# CPU.net
KiCad netlist of a schematic drawn in Altium Designer
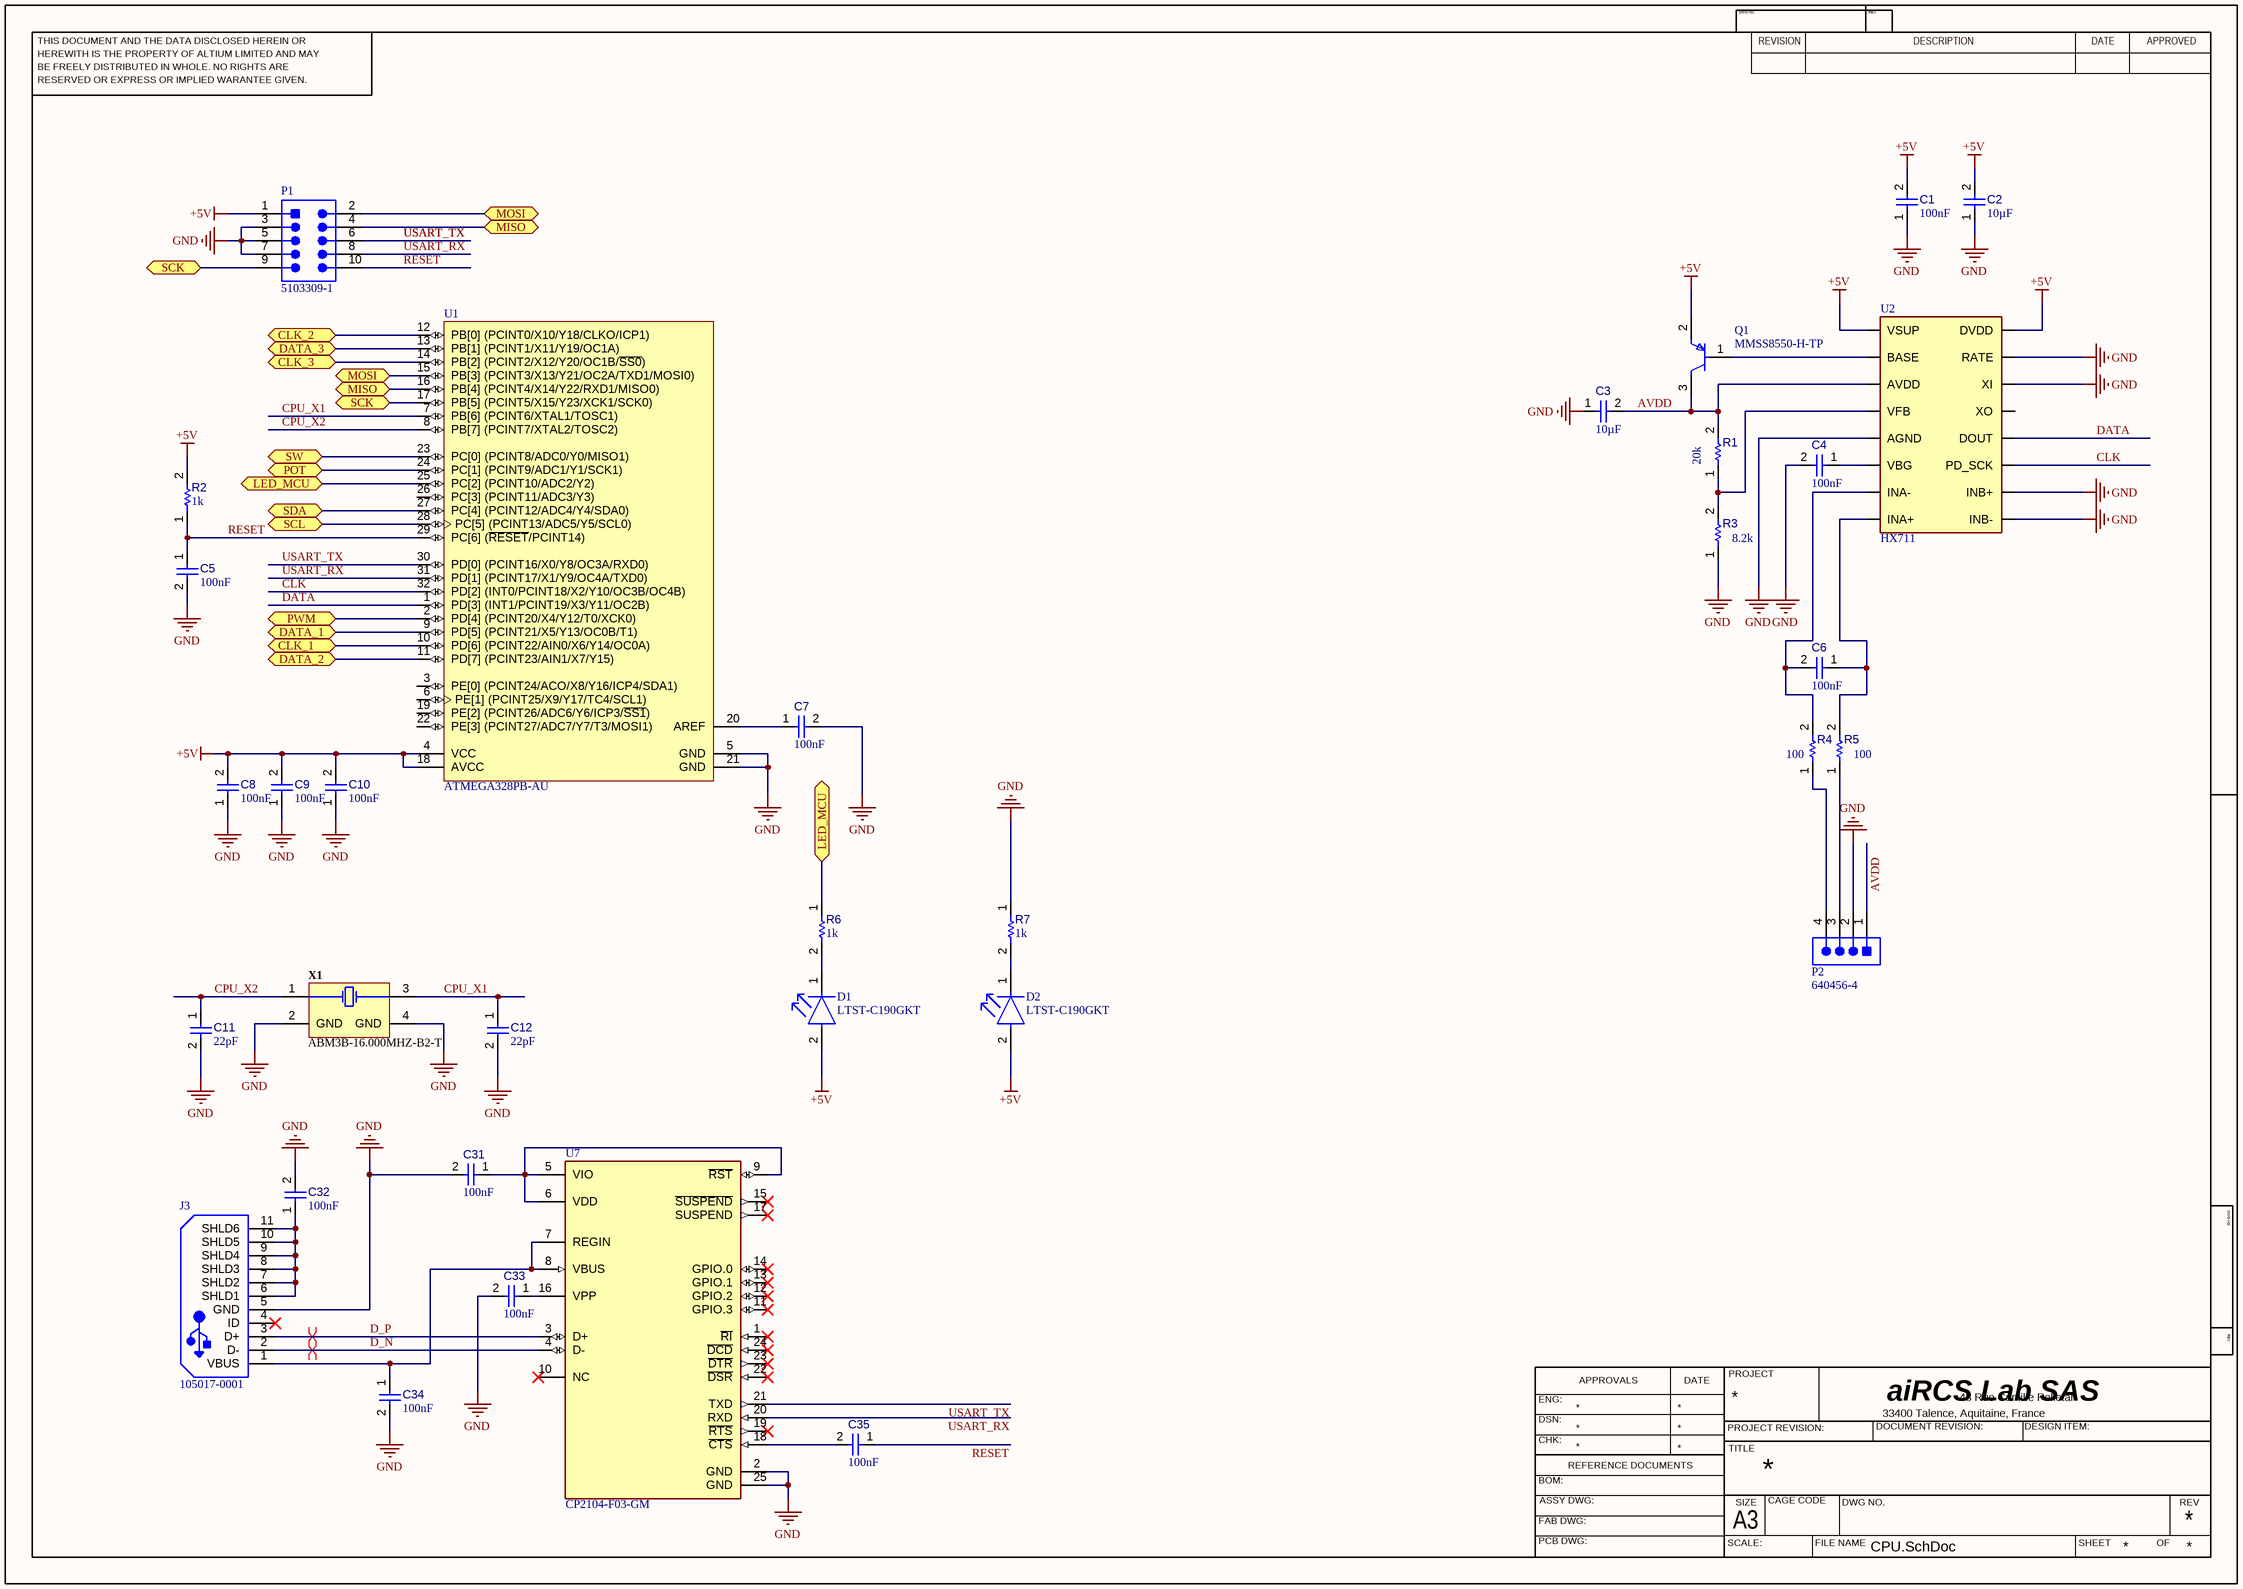
[diagram p0: CPU.SchDoc]

(export (version "E")
  (design (tool "Eeschema 10.0.6"))
  (components
    (comp (ref "C1")
      (value "100nF")
      (footprint "CAPC0402(1005)60_L")
      (description "Chip Capacitor, 100nF +/-20%, 50V, 0402, Thickness 0.6 mm")
      (fields (field (name "TOLERANCE") "10%") (field (name "Comment") "Capacitor 100nF +/-20% 50V 0402"))
      (libsource (lib "Kariboo") (part "CAP-NP-2"))
    )
    (comp (ref "C2")
      (value "10µF")
      (footprint "CAPC0402(1005)60_L")
      (description "Chip Capacitor, 10µF +/-40%, 6.3V, 0402, Thickness 0.6 mm")
      (fields (field (name "TOLERANCE") "10%") (field (name "Comment") "Capacitor 10µF +/-40% 6.3V 0402"))
      (libsource (lib "Kariboo") (part "CAP-NP-2"))
    )
    (comp (ref "C3")
      (value "10µF")
      (footprint "CAPC0402(1005)60_L")
      (description "Chip Capacitor, 10µF +/-40%, 6.3V, 0402, Thickness 0.6 mm")
      (fields (field (name "TOLERANCE") "10%") (field (name "Comment") "Capacitor 10µF +/-40% 6.3V 0402"))
      (libsource (lib "Kariboo") (part "CAP-NP-2"))
    )
    (comp (ref "C4")
      (value "100nF")
      (footprint "CAPC0402(1005)60_L")
      (description "Chip Capacitor, 100nF +/-20%, 50V, 0402, Thickness 0.6 mm")
      (fields (field (name "TOLERANCE") "10%") (field (name "Comment") "Capacitor 100nF +/-20% 50V 0402"))
      (libsource (lib "Kariboo") (part "CAP-NP-2"))
    )
    (comp (ref "C5")
      (value "100nF")
      (footprint "CAPC0402(1005)60_L")
      (description "Chip Capacitor, 100nF +/-20%, 50V, 0402, Thickness 0.6 mm")
      (fields (field (name "TOLERANCE") "10%") (field (name "Comment") "Capacitor 100nF +/-20% 50V 0402"))
      (libsource (lib "Kariboo") (part "CAP-NP-2"))
    )
    (comp (ref "C6")
      (value "100nF")
      (footprint "CAPC0402(1005)60_L")
      (description "Chip Capacitor, 100nF +/-20%, 50V, 0402, Thickness 0.6 mm")
      (fields (field (name "TOLERANCE") "10%") (field (name "Comment") "Capacitor 100nF +/-20% 50V 0402"))
      (libsource (lib "Kariboo") (part "CAP-NP-2"))
    )
    (comp (ref "C7")
      (value "100nF")
      (footprint "CAPC0402(1005)60_L")
      (description "Chip Capacitor, 100nF +/-20%, 50V, 0402, Thickness 0.6 mm")
      (fields (field (name "TOLERANCE") "10%") (field (name "Comment") "Capacitor 100nF +/-20% 50V 0402"))
      (libsource (lib "Kariboo") (part "CAP-NP-2"))
    )
    (comp (ref "C8")
      (value "100nF")
      (footprint "CAPC0402(1005)60_L")
      (description "Chip Capacitor, 100nF +/-20%, 50V, 0402, Thickness 0.6 mm")
      (fields (field (name "TOLERANCE") "10%") (field (name "Comment") "Capacitor 100nF +/-20% 50V 0402"))
      (libsource (lib "Kariboo") (part "CAP-NP-2"))
    )
    (comp (ref "C9")
      (value "100nF")
      (footprint "CAPC0402(1005)60_L")
      (description "Chip Capacitor, 100nF +/-20%, 50V, 0402, Thickness 0.6 mm")
      (fields (field (name "TOLERANCE") "10%") (field (name "Comment") "Capacitor 100nF +/-20% 50V 0402"))
      (libsource (lib "Kariboo") (part "CAP-NP-2"))
    )
    (comp (ref "C10")
      (value "100nF")
      (footprint "CAPC0402(1005)60_L")
      (description "Chip Capacitor, 100nF +/-20%, 50V, 0402, Thickness 0.6 mm")
      (fields (field (name "TOLERANCE") "10%") (field (name "Comment") "Capacitor 100nF +/-20% 50V 0402"))
      (libsource (lib "Kariboo") (part "CAP-NP-2"))
    )
    (comp (ref "C11")
      (value "22pF")
      (footprint "CAPC0603(1608)100_L")
      (description "Chip Capacitor, 1µF +/-40%, 50V, 0603, Thickness 1 mm")
      (fields (field (name "TOLERANCE") "10%") (field (name "Comment") "Capacitor 1µF +/-40% 50V 0603"))
      (libsource (lib "Kariboo") (part "CAP-NP-2"))
    )
    (comp (ref "C12")
      (value "22pF")
      (footprint "CAPC0603(1608)100_L")
      (description "Chip Capacitor, 1µF +/-40%, 50V, 0603, Thickness 1 mm")
      (fields (field (name "TOLERANCE") "10%") (field (name "Comment") "Capacitor 1µF +/-40% 50V 0603"))
      (libsource (lib "Kariboo") (part "CAP-NP-2"))
    )
    (comp (ref "C31")
      (value "100nF")
      (footprint "CAPC0603(1608)100_L")
      (description "Chip Capacitor, 1µF +/-40%, 50V, 0603, Thickness 1 mm")
      (fields (field (name "TOLERANCE") "10%") (field (name "Comment") "Capacitor 1µF +/-40% 50V 0603"))
      (libsource (lib "Kariboo") (part "CAP-NP-2"))
    )
    (comp (ref "C32")
      (value "100nF")
      (footprint "CAPC0603(1608)100_L")
      (description "Chip Capacitor, 1µF +/-40%, 50V, 0603, Thickness 1 mm")
      (fields (field (name "TOLERANCE") "10%") (field (name "Comment") "Capacitor 1µF +/-40% 50V 0603"))
      (libsource (lib "Kariboo") (part "CAP-NP-2"))
    )
    (comp (ref "C33")
      (value "100nF")
      (footprint "CAPC0603(1608)100_L")
      (description "Chip Capacitor, 1µF +/-40%, 50V, 0603, Thickness 1 mm")
      (fields (field (name "TOLERANCE") "10%") (field (name "Comment") "Capacitor 1µF +/-40% 50V 0603"))
      (libsource (lib "Kariboo") (part "CAP-NP-2"))
    )
    (comp (ref "C34")
      (value "100nF")
      (footprint "CAPC0603(1608)100_L")
      (description "Chip Capacitor, 1µF +/-40%, 50V, 0603, Thickness 1 mm")
      (fields (field (name "TOLERANCE") "10%") (field (name "Comment") "Capacitor 1µF +/-40% 50V 0603"))
      (libsource (lib "Kariboo") (part "CAP-NP-2"))
    )
    (comp (ref "C35")
      (value "100nF")
      (footprint "CAPC0603(1608)100_L")
      (description "Chip Capacitor, 1µF +/-40%, 50V, 0603, Thickness 1 mm")
      (fields (field (name "TOLERANCE") "10%") (field (name "Comment") "Capacitor 1µF +/-40% 50V 0603"))
      (libsource (lib "Kariboo") (part "CAP-NP-2"))
    )
    (comp (ref "D1")
      (value "LTST-C190GKT")
      (footprint "FP-LTST-C190GKT-MFG")
      (description "LED GREEN CLEAR CHIP SMD")
      (fields (field (name "VOLTAGE") "2V"))
      (libsource (lib "Altium Content Vault") (part "8706943c75ba83719d021d2fdc84c58"))
    )
    (comp (ref "D2")
      (value "LTST-C190GKT")
      (footprint "FP-LTST-C190GKT-MFG")
      (description "LED GREEN CLEAR CHIP SMD")
      (fields (field (name "VOLTAGE") "2V"))
      (libsource (lib "Altium Content Vault") (part "8706943c75ba83719d021d2fdc84c58"))
    )
    (comp (ref "J3")
      (value "105017-0001")
      (footprint "USB-MICRO-B_V")
      (fields (field (name "MANUFACTURER") "Molex"))
      (libsource (lib "Altium Content Vault") (part "USB-5-6SHLD"))
    )
    (comp (ref "P1")
      (value "5103309-1")
      (footprint "TECO-5103309-1_V")
      (fields (field (name "MANUFACTURER") "TE Connectivity"))
      (libsource (lib "Altium Content Vault") (part "CN-2P-M-R10"))
    )
    (comp (ref "P2")
      (value "640456-4")
      (footprint "TECO-640456-4")
      (description "Male Header, Pitch 2.54 mm, 1 x 4 Position, Height 10.03 mm, Tail Length 3.56 mm, RoHS, Bulk")
      (fields (field (name "MANUFACTURER") "TE Connectivity"))
      (libsource (lib "Altium Content Vault") (part "CN-1P-M-R4"))
    )
    (comp (ref "Q1")
      (value "MMSS8550-H-TP")
      (footprint "FP-SOT-23-IPC_B")
      (description "TRANS PNP 25V 1.5A SOT23")
      (libsource (lib "Altium Content Vault") (part "0e8486ed3b47d9c69b8404ba87cf0f7"))
    )
    (comp (ref "R1")
      (value "20k")
      (footprint "RESC0402(1005)_L")
      (description "Resistor 0402")
      (fields (field (name "Comment") "RES"))
      (libsource (lib "Kariboo") (part "0R2J"))
    )
    (comp (ref "R2") (value "1k") (footprint "RESC0402(1005)_L") (libsource (lib "Kariboo") (part "0R2J")))
    (comp (ref "R3")
      (value "8.2k")
      (footprint "RESC0402(1005)_L")
      (description "Resistor 0402")
      (libsource (lib "Kariboo") (part "0R2J"))
    )
    (comp (ref "R4") (value "100") (footprint "RESC0402(1005)_L") (libsource (lib "Kariboo") (part "0R2J")))
    (comp (ref "R5") (value "100") (footprint "RESC0402(1005)_L") (libsource (lib "Kariboo") (part "0R2J")))
    (comp (ref "R6") (value "1k") (footprint "RESC0402(1005)_L") (libsource (lib "Kariboo") (part "0R2J")))
    (comp (ref "R7") (value "1k") (footprint "RESC0402(1005)_L") (libsource (lib "Kariboo") (part "0R2J")))
    (comp (ref "U1")
      (value "ATMEGA328PB-AU")
      (footprint "ATML-32A_L")
      (fields (field (name "MANUFACTURER") "Microchip"))
      (libsource (lib "Altium Content Vault") (part "ATML-ATMEGA328PB-32A"))
    )
    (comp (ref "U2")
      (value "HX711")
      (footprint "SOP127P600X180-16N")
      (fields (field (name "MF") "AVIA SEMICONDUCTOR"))
      (libsource (lib "HX711") (part "HX711"))
    )
    (comp (ref "U7")
      (value "CP2104-F03-GM")
      (footprint "FP-CP2104-F03-GM-MFG")
      (description "IC SGL USB-TO-UART BRIDGE 24QFN")
      (libsource (lib "Altium Content Vault") (part "36aa9e967c7f1036f799a443da3d357"))
    )
    (comp (ref "X1")
      (value "ABM3B-16.000MHZ-B2-T")
      (footprint "ABRA-ABM3B-4_V")
      (description "Ceramic SMD Crystal, 16 MHz, +/- 20 ppm, 50 Ohm, -20 to 70 degC, 4-Pin SMD, RoHS, Tape and Reel")
      (fields (field (name "TOLERANCE") "30%"))
      (libsource (lib "Altium Content Vault") (part "XTAL-1-3-4"))
    )
  )
  (nets
    (net (code "1") (name "+5V") (class "Default")
      (node (ref "C1") (pin "2") (pinfunction "2_2") (pintype "passive"))
      (node (ref "C10") (pin "2") (pinfunction "2_2") (pintype "passive"))
      (node (ref "C2") (pin "2") (pinfunction "2_2") (pintype "passive"))
      (node (ref "C8") (pin "2") (pinfunction "2_2") (pintype "passive"))
      (node (ref "C9") (pin "2") (pinfunction "2_2") (pintype "passive"))
      (node (ref "D1") (pin "2") (pinfunction "A_2") (pintype "passive"))
      (node (ref "D2") (pin "2") (pinfunction "A_2") (pintype "passive"))
      (node (ref "P1") (pin "1") (pinfunction "1_1") (pintype "passive"))
      (node (ref "Q1") (pin "2") (pinfunction "E_2") (pintype "passive"))
      (node (ref "R2") (pin "2") (pinfunction "2_2") (pintype "passive"))
      (node (ref "U1") (pin "18") (pinfunction "AVCC_18") (pintype "power_in"))
      (node (ref "U1") (pin "4") (pinfunction "VCC_4") (pintype "power_in"))
      (node (ref "U2") (pin "1") (pinfunction "VSUP_1") (pintype "bidirectional"))
      (node (ref "U2") (pin "16") (pinfunction "DVDD_16") (pintype "bidirectional"))
    )
    (net (code "2") (name "/AVDD") (class "Default")
      (node (ref "C3") (pin "2") (pinfunction "2_2") (pintype "passive"))
      (node (ref "P2") (pin "1") (pinfunction "1_1") (pintype "passive"))
      (node (ref "Q1") (pin "3") (pinfunction "C_3") (pintype "passive"))
      (node (ref "R1") (pin "2") (pinfunction "2_2") (pintype "passive"))
      (node (ref "U2") (pin "3") (pinfunction "AVDD_3") (pintype "bidirectional"))
    )
    (net (code "3") (name "/CLK") (class "Default")
      (node (ref "U1") (pin "32") (pinfunction "PD[2]_(INT0/PCINT18/X2/Y10/OC3B/OC4B)_32") (pintype "bidirectional"))
      (node (ref "U2") (pin "11") (pinfunction "PD_SCK_11") (pintype "bidirectional"))
    )
    (net (code "4") (name "/CLK_1") (class "Default")
      (node (ref "U1") (pin "10") (pinfunction "PD[6]_(PCINT22/AIN0/X6/Y14/OC0A)_10") (pintype "bidirectional"))
    )
    (net (code "5") (name "/CLK_2") (class "Default")
      (node (ref "U1") (pin "12") (pinfunction "PB[0]_(PCINT0/X10/Y18/CLKO/ICP1)_12") (pintype "bidirectional"))
    )
    (net (code "6") (name "/CLK_3") (class "Default")
      (node (ref "U1") (pin "14") (pinfunction "PB[2]_(PCINT2/X12/Y20/OC1B/~{SS0})_14") (pintype "bidirectional"))
    )
    (net (code "7") (name "/CPU_X1") (class "Default")
      (node (ref "C12") (pin "1") (pinfunction "1_1") (pintype "passive"))
      (node (ref "U1") (pin "7") (pinfunction "PB[6]_(PCINT6/XTAL1/TOSC1)_7") (pintype "bidirectional"))
      (node (ref "X1") (pin "3") (pinfunction "X2_3") (pintype "passive"))
    )
    (net (code "8") (name "/CPU_X2") (class "Default")
      (node (ref "C11") (pin "1") (pinfunction "1_1") (pintype "passive"))
      (node (ref "U1") (pin "8") (pinfunction "PB[7]_(PCINT7/XTAL2/TOSC2)_8") (pintype "bidirectional"))
      (node (ref "X1") (pin "1") (pinfunction "X1_1") (pintype "passive"))
    )
    (net (code "9") (name "/DATA") (class "Default")
      (node (ref "U1") (pin "1") (pinfunction "PD[3]_(INT1/PCINT19/X3/Y11/OC2B)_1") (pintype "bidirectional"))
      (node (ref "U2") (pin "12") (pinfunction "DOUT_12") (pintype "bidirectional"))
    )
    (net (code "10") (name "/DATA_1") (class "Default")
      (node (ref "U1") (pin "9") (pinfunction "PD[5]_(PCINT21/X5/Y13/OC0B/T1)_9") (pintype "bidirectional"))
    )
    (net (code "11") (name "/DATA_2") (class "Default")
      (node (ref "U1") (pin "11") (pinfunction "PD[7]_(PCINT23/AIN1/X7/Y15)_11") (pintype "bidirectional"))
    )
    (net (code "12") (name "/DATA_3") (class "Default")
      (node (ref "U1") (pin "13") (pinfunction "PB[1]_(PCINT1/X11/Y19/OC1A)_13") (pintype "bidirectional"))
    )
    (net (code "13") (name "/D_N") (class "Default")
      (node (ref "J3") (pin "2") (pinfunction "D-_2") (pintype "passive"))
      (node (ref "U7") (pin "4") (pinfunction "D-_4") (pintype "bidirectional"))
    )
    (net (code "14") (name "/D_P") (class "Default")
      (node (ref "J3") (pin "3") (pinfunction "D+_3") (pintype "passive"))
      (node (ref "U7") (pin "3") (pinfunction "D+_3") (pintype "bidirectional"))
    )
    (net (code "15") (name "/LED_MCU") (class "Default")
      (node (ref "R6") (pin "1") (pinfunction "1_1") (pintype "passive"))
      (node (ref "U1") (pin "25") (pinfunction "PC[2]_(PCINT10/ADC2/Y2)_25") (pintype "bidirectional"))
    )
    (net (code "16") (name "/MISO") (class "Default")
      (node (ref "P1") (pin "4") (pinfunction "4_4") (pintype "passive"))
      (node (ref "U1") (pin "16") (pinfunction "PB[4]_(PCINT4/X14/Y22/RXD1/MISO0)_16") (pintype "bidirectional"))
    )
    (net (code "17") (name "/MOSI") (class "Default")
      (node (ref "P1") (pin "2") (pinfunction "2_2") (pintype "passive"))
      (node (ref "U1") (pin "15") (pinfunction "PB[3]_(PCINT3/X13/Y21/OC2A/TXD1/MOSI0)_15") (pintype "bidirectional"))
    )
    (net (code "18") (name "/POT") (class "Default")
      (node (ref "U1") (pin "24") (pinfunction "PC[1]_(PCINT9/ADC1/Y1/SCK1)_24") (pintype "bidirectional"))
    )
    (net (code "19") (name "/PWM") (class "Default")
      (node (ref "U1") (pin "2") (pinfunction "PD[4]_(PCINT20/X4/Y12/T0/XCK0)_2") (pintype "bidirectional"))
    )
    (net (code "20") (name "/RESET") (class "Default")
      (node (ref "C35") (pin "1") (pinfunction "1_1") (pintype "passive"))
      (node (ref "C5") (pin "1") (pinfunction "1_1") (pintype "passive"))
      (node (ref "P1") (pin "10") (pinfunction "10_10") (pintype "passive"))
      (node (ref "R2") (pin "1") (pinfunction "1_1") (pintype "passive"))
      (node (ref "U1") (pin "29") (pinfunction "PC[6]_(~{RESET}/PCINT14)_29") (pintype "bidirectional"))
    )
    (net (code "21") (name "/SCK") (class "Default")
      (node (ref "P1") (pin "9") (pinfunction "9_9") (pintype "passive"))
      (node (ref "U1") (pin "17") (pinfunction "PB[5]_(PCINT5/X15/Y23/XCK1/SCK0)_17") (pintype "bidirectional"))
    )
    (net (code "22") (name "/SCL") (class "Default")
      (node (ref "U1") (pin "28") (pinfunction "PC[5]_(PCINT13/ADC5/Y5/SCL0)_28") (pintype "bidirectional"))
    )
    (net (code "23") (name "/SDA") (class "Default")
      (node (ref "U1") (pin "27") (pinfunction "PC[4]_(PCINT12/ADC4/Y4/SDA0)_27") (pintype "bidirectional"))
    )
    (net (code "24") (name "/SW") (class "Default")
      (node (ref "U1") (pin "23") (pinfunction "PC[0]_(PCINT8/ADC0/Y0/MISO1)_23") (pintype "bidirectional"))
    )
    (net (code "25") (name "/USART_RX") (class "Default")
      (node (ref "P1") (pin "8") (pinfunction "8_8") (pintype "passive"))
      (node (ref "U1") (pin "31") (pinfunction "PD[1]_(PCINT17/X1/Y9/OC4A/TXD0)_31") (pintype "bidirectional"))
      (node (ref "U7") (pin "20") (pinfunction "RXD_20") (pintype "input"))
    )
    (net (code "26") (name "/USART_TX") (class "Default")
      (node (ref "P1") (pin "6") (pinfunction "6_6") (pintype "passive"))
      (node (ref "U1") (pin "30") (pinfunction "PD[0]_(PCINT16/X0/Y8/OC3A/RXD0)_30") (pintype "bidirectional"))
      (node (ref "U7") (pin "21") (pinfunction "TXD_21") (pintype "output"))
    )
    (net (code "27") (name "GND") (class "Default")
      (node (ref "C1") (pin "1") (pinfunction "1_1") (pintype "passive"))
      (node (ref "C10") (pin "1") (pinfunction "1_1") (pintype "passive"))
      (node (ref "C11") (pin "2") (pinfunction "2_2") (pintype "passive"))
      (node (ref "C12") (pin "2") (pinfunction "2_2") (pintype "passive"))
      (node (ref "C2") (pin "1") (pinfunction "1_1") (pintype "passive"))
      (node (ref "C3") (pin "1") (pinfunction "1_1") (pintype "passive"))
      (node (ref "C31") (pin "2") (pinfunction "2_2") (pintype "passive"))
      (node (ref "C32") (pin "2") (pinfunction "2_2") (pintype "passive"))
      (node (ref "C33") (pin "2") (pinfunction "2_2") (pintype "passive"))
      (node (ref "C34") (pin "2") (pinfunction "2_2") (pintype "passive"))
      (node (ref "C4") (pin "2") (pinfunction "2_2") (pintype "passive"))
      (node (ref "C5") (pin "2") (pinfunction "2_2") (pintype "passive"))
      (node (ref "C7") (pin "2") (pinfunction "2_2") (pintype "passive"))
      (node (ref "C8") (pin "1") (pinfunction "1_1") (pintype "passive"))
      (node (ref "C9") (pin "1") (pinfunction "1_1") (pintype "passive"))
      (node (ref "J3") (pin "5") (pinfunction "GND_5") (pintype "passive"))
      (node (ref "P1") (pin "3") (pinfunction "3_3") (pintype "passive"))
      (node (ref "P1") (pin "5") (pinfunction "5_5") (pintype "passive"))
      (node (ref "P1") (pin "7") (pinfunction "7_7") (pintype "passive"))
      (node (ref "P2") (pin "2") (pinfunction "2_2") (pintype "passive"))
      (node (ref "R3") (pin "1") (pinfunction "1_1") (pintype "passive"))
      (node (ref "R7") (pin "1") (pinfunction "1_1") (pintype "passive"))
      (node (ref "U1") (pin "21") (pinfunction "GND_21") (pintype "power_in"))
      (node (ref "U1") (pin "5") (pinfunction "GND_5") (pintype "power_in"))
      (node (ref "U2") (pin "10") (pinfunction "INB+_10") (pintype "bidirectional"))
      (node (ref "U2") (pin "14") (pinfunction "XI_14") (pintype "bidirectional"))
      (node (ref "U2") (pin "15") (pinfunction "RATE_15") (pintype "bidirectional"))
      (node (ref "U2") (pin "5") (pinfunction "AGND_5") (pintype "bidirectional"))
      (node (ref "U2") (pin "9") (pinfunction "INB-_9") (pintype "bidirectional"))
      (node (ref "U7") (pin "2") (pinfunction "GND_2") (pintype "power_in"))
      (node (ref "U7") (pin "25") (pinfunction "GND_25") (pintype "power_in"))
      (node (ref "X1") (pin "2") (pinfunction "GND_2") (pintype "power_in"))
      (node (ref "X1") (pin "4") (pinfunction "GND_4") (pintype "power_in"))
    )
    (net (code "28") (name "Net-(D1-C)") (class "Default")
      (node (ref "D1") (pin "1") (pinfunction "C_1") (pintype "passive"))
      (node (ref "R6") (pin "2") (pinfunction "2_2") (pintype "passive"))
    )
    (net (code "29") (name "Net-(D2-C)") (class "Default")
      (node (ref "D2") (pin "1") (pinfunction "C_1") (pintype "passive"))
      (node (ref "R7") (pin "2") (pinfunction "2_2") (pintype "passive"))
    )
    (net (code "30") (name "Net-(J3-SHLD1)") (class "Default")
      (node (ref "C32") (pin "1") (pinfunction "1_1") (pintype "passive"))
      (node (ref "J3") (pin "10") (pinfunction "SHLD5_10") (pintype "passive"))
      (node (ref "J3") (pin "11") (pinfunction "SHLD6_11") (pintype "passive"))
      (node (ref "J3") (pin "6") (pinfunction "SHLD1_6") (pintype "passive"))
      (node (ref "J3") (pin "7") (pinfunction "SHLD2_7") (pintype "passive"))
      (node (ref "J3") (pin "8") (pinfunction "SHLD3_8") (pintype "passive"))
      (node (ref "J3") (pin "9") (pinfunction "SHLD4_9") (pintype "passive"))
    )
    (net (code "31") (name "Net-(J3-VBUS)") (class "Default")
      (node (ref "C34") (pin "1") (pinfunction "1_1") (pintype "passive"))
      (node (ref "J3") (pin "1") (pinfunction "VBUS_1") (pintype "passive"))
      (node (ref "U7") (pin "7") (pinfunction "REGIN_7") (pintype "power_in"))
      (node (ref "U7") (pin "8") (pinfunction "VBUS_8") (pintype "input"))
    )
    (net (code "32") (name "Net-(P2-Pad3)") (class "Default")
      (node (ref "P2") (pin "3") (pinfunction "3_3") (pintype "passive"))
      (node (ref "R5") (pin "1") (pinfunction "1_1") (pintype "passive"))
    )
    (net (code "33") (name "Net-(P2-Pad4)") (class "Default")
      (node (ref "P2") (pin "4") (pinfunction "4_4") (pintype "passive"))
      (node (ref "R4") (pin "1") (pinfunction "1_1") (pintype "passive"))
    )
    (net (code "34") (name "Net-(Q1-B)") (class "Default")
      (node (ref "Q1") (pin "1") (pinfunction "B_1") (pintype "passive"))
      (node (ref "U2") (pin "2") (pinfunction "BASE_2") (pintype "bidirectional"))
    )
    (net (code "35") (name "Net-(U1-AREF)") (class "Default")
      (node (ref "C7") (pin "1") (pinfunction "1_1") (pintype "passive"))
      (node (ref "U1") (pin "20") (pinfunction "AREF_20") (pintype "passive"))
    )
    (net (code "36") (name "Net-(U2-INA+)") (class "Default")
      (node (ref "C6") (pin "1") (pinfunction "1_1") (pintype "passive"))
      (node (ref "R5") (pin "2") (pinfunction "2_2") (pintype "passive"))
      (node (ref "U2") (pin "8") (pinfunction "INA+_8") (pintype "bidirectional"))
    )
    (net (code "37") (name "Net-(U2-INA-)") (class "Default")
      (node (ref "C6") (pin "2") (pinfunction "2_2") (pintype "passive"))
      (node (ref "R4") (pin "2") (pinfunction "2_2") (pintype "passive"))
      (node (ref "U2") (pin "7") (pinfunction "INA-_7") (pintype "bidirectional"))
    )
    (net (code "38") (name "Net-(U2-VBG)") (class "Default")
      (node (ref "C4") (pin "1") (pinfunction "1_1") (pintype "passive"))
      (node (ref "U2") (pin "6") (pinfunction "VBG_6") (pintype "bidirectional"))
    )
    (net (code "39") (name "Net-(U2-VFB)") (class "Default")
      (node (ref "R1") (pin "1") (pinfunction "1_1") (pintype "passive"))
      (node (ref "R3") (pin "2") (pinfunction "2_2") (pintype "passive"))
      (node (ref "U2") (pin "4") (pinfunction "VFB_4") (pintype "bidirectional"))
    )
    (net (code "40") (name "Net-(U7-VDD)") (class "Default")
      (node (ref "C31") (pin "1") (pinfunction "1_1") (pintype "passive"))
      (node (ref "U7") (pin "5") (pinfunction "VIO_5") (pintype "power_in"))
      (node (ref "U7") (pin "6") (pinfunction "VDD_6") (pintype "power_in"))
      (node (ref "U7") (pin "9") (pinfunction "~{RST}_9") (pintype "bidirectional"))
    )
    (net (code "41") (name "Net-(U7-VPP)") (class "Default")
      (node (ref "C33") (pin "1") (pinfunction "1_1") (pintype "passive"))
      (node (ref "U7") (pin "16") (pinfunction "VPP_16") (pintype "passive"))
    )
    (net (code "42") (name "Net-(U7-~{CTS})") (class "Default")
      (node (ref "C35") (pin "2") (pinfunction "2_2") (pintype "passive"))
      (node (ref "U7") (pin "18") (pinfunction "~{CTS}_18") (pintype "input"))
    )
    (net (code "43") (name "unconnected-(J3-ID-Pad4)") (class "Default")
      (node (ref "J3") (pin "4") (pinfunction "ID_4") (pintype "passive+no_connect"))
    )
    (net (code "44") (name "unconnected-(U1-PC[3]_(PCINT11{slash}ADC3{slash}Y3)-Pad26)") (class "Default")
      (node (ref "U1") (pin "26") (pinfunction "PC[3]_(PCINT11/ADC3/Y3)_26") (pintype "bidirectional"))
    )
    (net (code "45") (name "unconnected-(U1-PE[0]_(PCINT24{slash}ACO{slash}X8{slash}Y16{slash}ICP4{slash}SDA1)-Pad3)") (class "Default")
      (node (ref "U1") (pin "3") (pinfunction "PE[0]_(PCINT24/ACO/X8/Y16/ICP4/SDA1)_3") (pintype "bidirectional"))
    )
    (net (code "46") (name "unconnected-(U1-PE[1]_(PCINT25{slash}X9{slash}Y17{slash}TC4{slash}SCL1)-Pad6)") (class "Default")
      (node (ref "U1") (pin "6") (pinfunction "PE[1]_(PCINT25/X9/Y17/TC4/SCL1)_6") (pintype "bidirectional"))
    )
    (net (code "47") (name "unconnected-(U1-PE[2]_(PCINT26{slash}ADC6{slash}Y6{slash}ICP3{slash}~{SS1})-Pad19)") (class "Default")
      (node (ref "U1") (pin "19") (pinfunction "PE[2]_(PCINT26/ADC6/Y6/ICP3/~{SS1})_19") (pintype "bidirectional"))
    )
    (net (code "48") (name "unconnected-(U1-PE[3]_(PCINT27{slash}ADC7{slash}Y7{slash}T3{slash}MOSI1)-Pad22)") (class "Default")
      (node (ref "U1") (pin "22") (pinfunction "PE[3]_(PCINT27/ADC7/Y7/T3/MOSI1)_22") (pintype "bidirectional"))
    )
    (net (code "49") (name "unconnected-(U2-XO-Pad13)") (class "Default")
      (node (ref "U2") (pin "13") (pinfunction "XO_13") (pintype "bidirectional"))
    )
    (net (code "50") (name "unconnected-(U7-GPIO.0-Pad14)") (class "Default")
      (node (ref "U7") (pin "14") (pinfunction "GPIO.0_14") (pintype "bidirectional+no_connect"))
    )
    (net (code "51") (name "unconnected-(U7-GPIO.1-Pad13)") (class "Default")
      (node (ref "U7") (pin "13") (pinfunction "GPIO.1_13") (pintype "bidirectional+no_connect"))
    )
    (net (code "52") (name "unconnected-(U7-GPIO.2-Pad12)") (class "Default")
      (node (ref "U7") (pin "12") (pinfunction "GPIO.2_12") (pintype "bidirectional+no_connect"))
    )
    (net (code "53") (name "unconnected-(U7-GPIO.3-Pad11)") (class "Default")
      (node (ref "U7") (pin "11") (pinfunction "GPIO.3_11") (pintype "bidirectional+no_connect"))
    )
    (net (code "54") (name "unconnected-(U7-NC-Pad10)") (class "Default")
      (node (ref "U7") (pin "10") (pinfunction "NC_10") (pintype "passive+no_connect"))
    )
    (net (code "55") (name "unconnected-(U7-SUSPEND-Pad17)") (class "Default")
      (node (ref "U7") (pin "17") (pinfunction "SUSPEND_17") (pintype "output+no_connect"))
    )
    (net (code "56") (name "unconnected-(U7-~{DCD}-Pad24)") (class "Default")
      (node (ref "U7") (pin "24") (pinfunction "~{DCD}_24") (pintype "input+no_connect"))
    )
    (net (code "57") (name "unconnected-(U7-~{DSR}-Pad22)") (class "Default")
      (node (ref "U7") (pin "22") (pinfunction "~{DSR}_22") (pintype "input+no_connect"))
    )
    (net (code "58") (name "unconnected-(U7-~{DTR}-Pad23)") (class "Default")
      (node (ref "U7") (pin "23") (pinfunction "~{DTR}_23") (pintype "output+no_connect"))
    )
    (net (code "59") (name "unconnected-(U7-~{RI}-Pad1)") (class "Default")
      (node (ref "U7") (pin "1") (pinfunction "~{RI}_1") (pintype "input+no_connect"))
    )
    (net (code "60") (name "unconnected-(U7-~{RTS}-Pad19)") (class "Default")
      (node (ref "U7") (pin "19") (pinfunction "~{RTS}_19") (pintype "output+no_connect"))
    )
    (net (code "61") (name "unconnected-(U7-~{SUSPEND}-Pad15)") (class "Default")
      (node (ref "U7") (pin "15") (pinfunction "~{SUSPEND}_15") (pintype "output+no_connect"))
    )
  )
)
